# r8_1.net
KiCad netlist of a schematic drawn in EAGLE
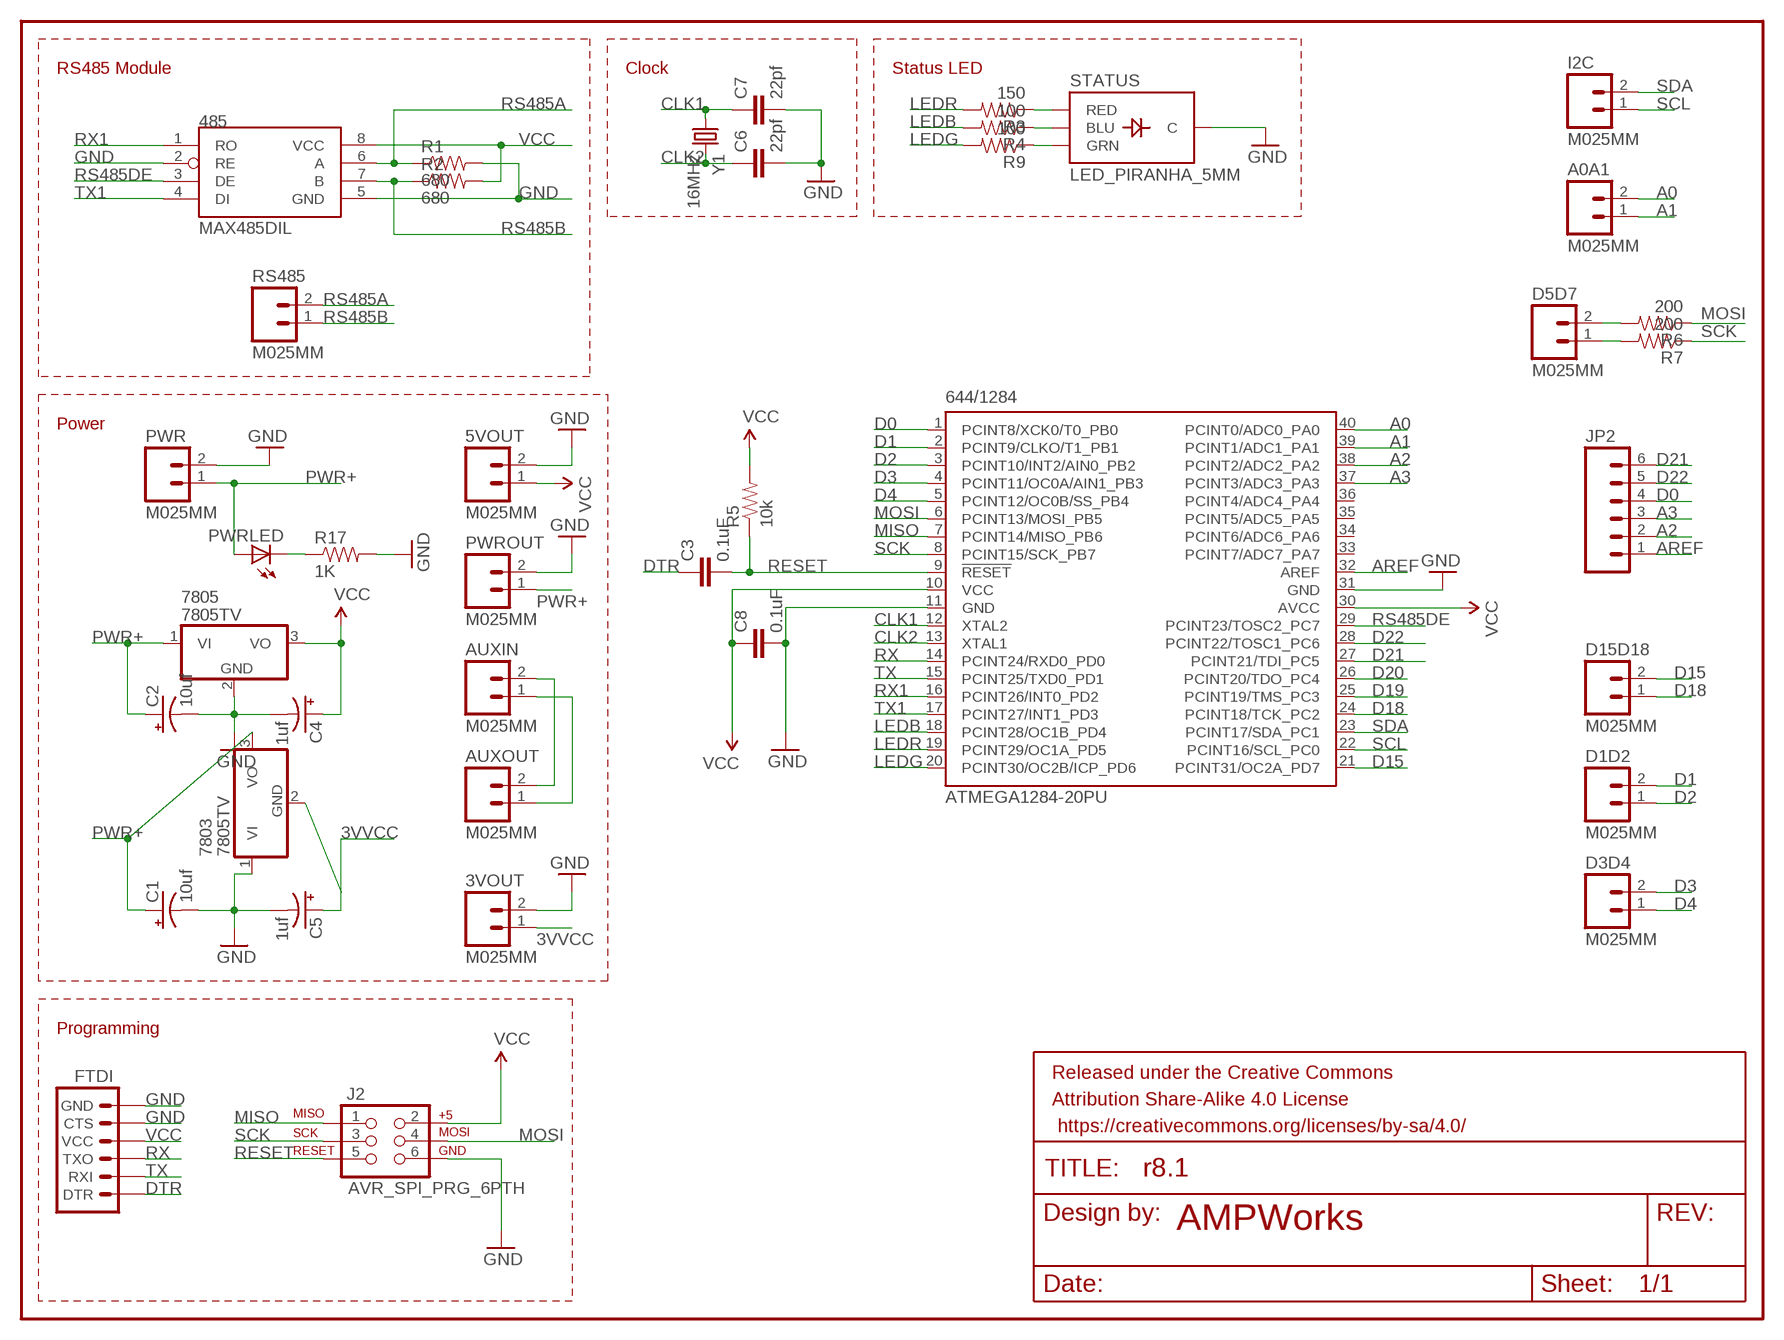
[diagram p0: schematic, sheet 1]

(export (version "E")
  (design (tool "Eeschema 10.0.6"))
  (components
    (comp (ref "3VOUT")
      (value "M025MM")
      (footprint "eagle-import:SCREWTERMINAL-5MM-2")
      (libsource (lib "eagle-import") (part "M025MM"))
    )
    (comp (ref "5VOUT")
      (value "M025MM")
      (footprint "eagle-import:SCREWTERMINAL-5MM-2")
      (libsource (lib "eagle-import") (part "M025MM"))
    )
    (comp (ref "485")
      (value "MAX485DIL")
      (footprint "eagle-import:DIL08")
      (libsource (lib "eagle-import") (part "MAX485DIL"))
    )
    (comp (ref "644/1284")
      (value "ATMEGA1284-20PU")
      (footprint "eagle-import:DIL40")
      (fields (field (name "MPN") "ATMEGA644-20PU"))
      (libsource (lib "eagle-import") (part "ATMEGA644-PU20"))
    )
    (comp (ref "7803")
      (value "7805TV")
      (footprint "eagle-import:TO220V")
      (libsource (lib "eagle-import") (part "78TV05"))
    )
    (comp (ref "7805")
      (value "7805TV")
      (footprint "eagle-import:TO220V")
      (libsource (lib "eagle-import") (part "78TV05"))
    )
    (comp (ref "A0A1")
      (value "M025MM")
      (footprint "eagle-import:SCREWTERMINAL-5MM-2")
      (libsource (lib "eagle-import") (part "M025MM"))
    )
    (comp (ref "AUXIN")
      (value "M025MM")
      (footprint "eagle-import:SCREWTERMINAL-5MM-2")
      (libsource (lib "eagle-import") (part "M025MM"))
    )
    (comp (ref "AUXOUT")
      (value "M025MM")
      (footprint "eagle-import:SCREWTERMINAL-5MM-2")
      (libsource (lib "eagle-import") (part "M025MM"))
    )
    (comp (ref "C1")
      (value "10uf")
      (footprint "eagle-import:CPOL-RADIAL-10UF-25V")
      (libsource (lib "eagle-import") (part "CAP_POLPTH2"))
    )
    (comp (ref "C2")
      (value "10uf")
      (footprint "eagle-import:CPOL-RADIAL-10UF-25V")
      (libsource (lib "eagle-import") (part "CAP_POLPTH2"))
    )
    (comp (ref "C3")
      (value "0.1uF")
      (footprint "eagle-import:CAP-PTH-SMALL")
      (libsource (lib "eagle-import") (part "CAPPTH"))
    )
    (comp (ref "C4")
      (value "1uf")
      (footprint "eagle-import:CPOL-RADIAL-10UF-25V")
      (libsource (lib "eagle-import") (part "CAP_POLPTH2"))
    )
    (comp (ref "C5")
      (value "1uf")
      (footprint "eagle-import:CPOL-RADIAL-10UF-25V")
      (libsource (lib "eagle-import") (part "CAP_POLPTH2"))
    )
    (comp (ref "C6")
      (value "22pf")
      (footprint "eagle-import:CAP-PTH-SMALL")
      (libsource (lib "eagle-import") (part "CAPPTH"))
    )
    (comp (ref "C7")
      (value "22pf")
      (footprint "eagle-import:CAP-PTH-SMALL")
      (libsource (lib "eagle-import") (part "CAPPTH"))
    )
    (comp (ref "C8")
      (value "0.1uF")
      (footprint "eagle-import:CAP-PTH-SMALL")
      (libsource (lib "eagle-import") (part "CAPPTH"))
    )
    (comp (ref "D1D2")
      (value "M025MM")
      (footprint "eagle-import:SCREWTERMINAL-5MM-2")
      (libsource (lib "eagle-import") (part "M025MM"))
    )
    (comp (ref "D3D4")
      (value "M025MM")
      (footprint "eagle-import:SCREWTERMINAL-5MM-2")
      (libsource (lib "eagle-import") (part "M025MM"))
    )
    (comp (ref "D5D7")
      (value "M025MM")
      (footprint "eagle-import:SCREWTERMINAL-5MM-2")
      (libsource (lib "eagle-import") (part "M025MM"))
    )
    (comp (ref "D15D18")
      (value "M025MM")
      (footprint "eagle-import:SCREWTERMINAL-5MM-2")
      (libsource (lib "eagle-import") (part "M025MM"))
    )
    (comp (ref "FRAME1")
      (value "FRAME-LETTER")
      (footprint "eagle-import:CREATIVE_COMMONS")
      (libsource (lib "eagle-import") (part "FRAME-LETTER"))
    )
    (comp (ref "FTDI")
      (value "ARDUINO_SERIAL_PROGRAMPTH")
      (footprint "eagle-import:1X06")
      (libsource (lib "eagle-import") (part "ARDUINO_SERIAL_PROGRAMPTH"))
    )
    (comp (ref "I2C")
      (value "M025MM")
      (footprint "eagle-import:SCREWTERMINAL-5MM-2")
      (libsource (lib "eagle-import") (part "M025MM"))
    )
    (comp (ref "J2")
      (value "AVR_SPI_PRG_6PTH")
      (footprint "eagle-import:2X3")
      (libsource (lib "eagle-import") (part "AVR_SPI_PRG_6PTH"))
    )
    (comp (ref "JP2")
      (value "M06NO_SILK")
      (footprint "eagle-import:1X06_NO_SILK")
      (libsource (lib "eagle-import") (part "M06NO_SILK"))
    )
    (comp (ref "PWR")
      (value "M025MM")
      (footprint "eagle-import:SCREWTERMINAL-5MM-2")
      (libsource (lib "eagle-import") (part "M025MM"))
    )
    (comp (ref "PWRLED")
      (value "LED5MM")
      (footprint "eagle-import:LED5MM")
      (libsource (lib "eagle-import") (part "LED5MM"))
    )
    (comp (ref "PWROUT")
      (value "M025MM")
      (footprint "eagle-import:SCREWTERMINAL-5MM-2")
      (libsource (lib "eagle-import") (part "M025MM"))
    )
    (comp (ref "R1")
      (value "680")
      (footprint "eagle-import:AXIAL-0.4")
      (libsource (lib "eagle-import") (part "SparkFun-Resistors_RESISTORPTH-1/4W"))
    )
    (comp (ref "R2")
      (value "680")
      (footprint "eagle-import:AXIAL-0.4")
      (libsource (lib "eagle-import") (part "SparkFun-Resistors_RESISTORPTH-1/4W"))
    )
    (comp (ref "R3")
      (value "150")
      (footprint "eagle-import:AXIAL-0.4")
      (libsource (lib "eagle-import") (part "RESISTORPTH-1/4W"))
    )
    (comp (ref "R4")
      (value "100")
      (footprint "eagle-import:AXIAL-0.4")
      (libsource (lib "eagle-import") (part "RESISTORPTH-1/4W"))
    )
    (comp (ref "R5")
      (value "10k")
      (footprint "eagle-import:AXIAL-0.4")
      (libsource (lib "eagle-import") (part "RESISTORPTH-1/4W"))
    )
    (comp (ref "R6")
      (value "200")
      (footprint "eagle-import:AXIAL-0.4")
      (libsource (lib "eagle-import") (part "RESISTORPTH-1/4W"))
    )
    (comp (ref "R7")
      (value "200")
      (footprint "eagle-import:AXIAL-0.4")
      (libsource (lib "eagle-import") (part "RESISTORPTH-1/4W"))
    )
    (comp (ref "R9")
      (value "100")
      (footprint "eagle-import:AXIAL-0.4")
      (libsource (lib "eagle-import") (part "RESISTORPTH-1/4W"))
    )
    (comp (ref "R17")
      (value "1K")
      (footprint "eagle-import:AXIAL-0.4")
      (libsource (lib "eagle-import") (part "SparkFun-Resistors_RESISTORPTH-1/4W"))
    )
    (comp (ref "RS485")
      (value "M025MM")
      (footprint "eagle-import:SCREWTERMINAL-5MM-2")
      (libsource (lib "eagle-import") (part "M025MM"))
    )
    (comp (ref "STATUS")
      (value "LED_PIRANHA_5MM")
      (footprint "eagle-import:LED_PIRANHA_5MM")
      (libsource (lib "eagle-import") (part "LED_PIRANHA_5MM"))
    )
    (comp (ref "Y1")
      (value "16MHz")
      (footprint "eagle-import:HC49US")
      (libsource (lib "eagle-import") (part "CRYSTALHC49US"))
    )
  )
  (nets
    (net (code "1") (name "/3VVCC") (class "Default")
      (node (ref "3VOUT") (pin "1") (pinfunction "1_1") (pintype "passive"))
      (node (ref "7803") (pin "2") (pinfunction "GND_2") (pintype "passive"))
      (node (ref "C5") (pin "1") (pinfunction "+_1") (pintype "passive"))
    )
    (net (code "2") (name "/A0") (class "Default")
      (node (ref "644/1284") (pin "40") (pinfunction "PCINT0/ADC0_PA0_40") (pintype "bidirectional"))
      (node (ref "A0A1") (pin "2") (pinfunction "2_2") (pintype "passive"))
    )
    (net (code "3") (name "/A1") (class "Default")
      (node (ref "644/1284") (pin "39") (pinfunction "PCINT1/ADC1_PA1_39") (pintype "bidirectional"))
      (node (ref "A0A1") (pin "1") (pinfunction "1_1") (pintype "passive"))
    )
    (net (code "4") (name "/A2") (class "Default")
      (node (ref "644/1284") (pin "38") (pinfunction "PCINT2/ADC2_PA2_38") (pintype "bidirectional"))
      (node (ref "JP2") (pin "2") (pinfunction "2_2") (pintype "passive"))
    )
    (net (code "5") (name "/A3") (class "Default")
      (node (ref "644/1284") (pin "37") (pinfunction "PCINT3/ADC3_PA3_37") (pintype "bidirectional"))
      (node (ref "JP2") (pin "3") (pinfunction "3_3") (pintype "passive"))
    )
    (net (code "6") (name "/AREF") (class "Default")
      (node (ref "644/1284") (pin "32") (pinfunction "AREF_32") (pintype "passive"))
      (node (ref "JP2") (pin "1") (pinfunction "1_1") (pintype "passive"))
    )
    (net (code "7") (name "/CLK1") (class "Default")
      (node (ref "644/1284") (pin "12") (pinfunction "XTAL2_12") (pintype "output"))
      (node (ref "C7") (pin "1") (pinfunction "1_1") (pintype "passive"))
      (node (ref "Y1") (pin "1") (pinfunction "1_1") (pintype "passive"))
    )
    (net (code "8") (name "/CLK2") (class "Default")
      (node (ref "644/1284") (pin "13") (pinfunction "XTAL1_13") (pintype "input"))
      (node (ref "C6") (pin "1") (pinfunction "1_1") (pintype "passive"))
      (node (ref "Y1") (pin "2") (pinfunction "2_2") (pintype "passive"))
    )
    (net (code "9") (name "/D0") (class "Default")
      (node (ref "644/1284") (pin "1") (pinfunction "PCINT8/XCK0/T0_PB0_1") (pintype "bidirectional"))
      (node (ref "JP2") (pin "4") (pinfunction "4_4") (pintype "passive"))
    )
    (net (code "10") (name "/D1") (class "Default")
      (node (ref "644/1284") (pin "2") (pinfunction "PCINT9/CLKO/T1_PB1_2") (pintype "bidirectional"))
      (node (ref "D1D2") (pin "2") (pinfunction "2_2") (pintype "passive"))
    )
    (net (code "11") (name "/D2") (class "Default")
      (node (ref "644/1284") (pin "3") (pinfunction "PCINT10/INT2/AIN0_PB2_3") (pintype "bidirectional"))
      (node (ref "D1D2") (pin "1") (pinfunction "1_1") (pintype "passive"))
    )
    (net (code "12") (name "/D3") (class "Default")
      (node (ref "644/1284") (pin "4") (pinfunction "PCINT11/OC0A/AIN1_PB3_4") (pintype "bidirectional"))
      (node (ref "D3D4") (pin "2") (pinfunction "2_2") (pintype "passive"))
    )
    (net (code "13") (name "/D4") (class "Default")
      (node (ref "644/1284") (pin "5") (pinfunction "PCINT12/OC0B/SS_PB4_5") (pintype "bidirectional"))
      (node (ref "D3D4") (pin "1") (pinfunction "1_1") (pintype "passive"))
    )
    (net (code "14") (name "/D15") (class "Default")
      (node (ref "644/1284") (pin "21") (pinfunction "PCINT31/OC2A_PD7_21") (pintype "bidirectional"))
      (node (ref "D15D18") (pin "2") (pinfunction "2_2") (pintype "passive"))
    )
    (net (code "15") (name "/D18") (class "Default")
      (node (ref "644/1284") (pin "24") (pinfunction "PCINT18/TCK_PC2_24") (pintype "bidirectional"))
      (node (ref "D15D18") (pin "1") (pinfunction "1_1") (pintype "passive"))
    )
    (net (code "16") (name "/D19") (class "Default")
      (node (ref "644/1284") (pin "25") (pinfunction "PCINT19/TMS_PC3_25") (pintype "bidirectional"))
    )
    (net (code "17") (name "/D20") (class "Default")
      (node (ref "644/1284") (pin "26") (pinfunction "PCINT20/TDO_PC4_26") (pintype "bidirectional"))
    )
    (net (code "18") (name "/D21") (class "Default")
      (node (ref "644/1284") (pin "27") (pinfunction "PCINT21/TDI_PC5_27") (pintype "bidirectional"))
      (node (ref "JP2") (pin "6") (pinfunction "6_6") (pintype "passive"))
    )
    (net (code "19") (name "/D22") (class "Default")
      (node (ref "644/1284") (pin "28") (pinfunction "PCINT22/TOSC1_PC6_28") (pintype "bidirectional"))
      (node (ref "JP2") (pin "5") (pinfunction "5_5") (pintype "passive"))
    )
    (net (code "20") (name "/DTR") (class "Default")
      (node (ref "C3") (pin "1") (pinfunction "1_1") (pintype "passive"))
      (node (ref "FTDI") (pin "DTR") (pinfunction "DTR_DTR") (pintype "passive"))
    )
    (net (code "21") (name "/LEDB") (class "Default")
      (node (ref "644/1284") (pin "18") (pinfunction "PCINT28/OC1B_PD4_18") (pintype "bidirectional"))
      (node (ref "R4") (pin "P$2") (pinfunction "2_P$2") (pintype "passive"))
    )
    (net (code "22") (name "/LEDG") (class "Default")
      (node (ref "644/1284") (pin "20") (pinfunction "PCINT30/OC2B/ICP_PD6_20") (pintype "bidirectional"))
      (node (ref "R9") (pin "P$2") (pinfunction "2_P$2") (pintype "passive"))
    )
    (net (code "23") (name "/LEDR") (class "Default")
      (node (ref "644/1284") (pin "19") (pinfunction "PCINT29/OC1A_PD5_19") (pintype "bidirectional"))
      (node (ref "R3") (pin "P$2") (pinfunction "2_P$2") (pintype "passive"))
    )
    (net (code "24") (name "/MISO") (class "Default")
      (node (ref "644/1284") (pin "7") (pinfunction "PCINT14/MISO_PB6_7") (pintype "bidirectional"))
      (node (ref "J2") (pin "1") (pinfunction "1_1") (pintype "passive"))
    )
    (net (code "25") (name "/MOSI") (class "Default")
      (node (ref "644/1284") (pin "6") (pinfunction "PCINT13/MOSI_PB5_6") (pintype "bidirectional"))
      (node (ref "J2") (pin "4") (pinfunction "4_4") (pintype "passive"))
      (node (ref "R6") (pin "P$1") (pinfunction "1_P$1") (pintype "passive"))
    )
    (net (code "26") (name "/PWR+") (class "Default")
      (node (ref "7803") (pin "3") (pinfunction "VO_3") (pintype "passive"))
      (node (ref "7805") (pin "1") (pinfunction "VI_1") (pintype "input"))
      (node (ref "C1") (pin "1") (pinfunction "+_1") (pintype "passive"))
      (node (ref "C2") (pin "1") (pinfunction "+_1") (pintype "passive"))
      (node (ref "PWR") (pin "1") (pinfunction "1_1") (pintype "passive"))
      (node (ref "PWRLED") (pin "A") (pinfunction "A_A") (pintype "passive"))
      (node (ref "PWROUT") (pin "1") (pinfunction "1_1") (pintype "passive"))
    )
    (net (code "27") (name "/RESET") (class "Default")
      (node (ref "644/1284") (pin "9") (pinfunction "~{RESET}_9") (pintype "input"))
      (node (ref "C3") (pin "2") (pinfunction "2_2") (pintype "passive"))
      (node (ref "J2") (pin "5") (pinfunction "5_5") (pintype "passive"))
      (node (ref "R5") (pin "P$1") (pinfunction "1_P$1") (pintype "passive"))
    )
    (net (code "28") (name "/RS485A") (class "Default")
      (node (ref "485") (pin "6") (pinfunction "A_6") (pintype "bidirectional"))
      (node (ref "R1") (pin "P$1") (pinfunction "1_P$1") (pintype "passive"))
      (node (ref "RS485") (pin "2") (pinfunction "2_2") (pintype "passive"))
    )
    (net (code "29") (name "/RS485B") (class "Default")
      (node (ref "485") (pin "7") (pinfunction "B_7") (pintype "bidirectional"))
      (node (ref "R2") (pin "P$1") (pinfunction "1_P$1") (pintype "passive"))
      (node (ref "RS485") (pin "1") (pinfunction "1_1") (pintype "passive"))
    )
    (net (code "30") (name "/RS485DE") (class "Default")
      (node (ref "485") (pin "3") (pinfunction "DE_3") (pintype "bidirectional"))
      (node (ref "644/1284") (pin "29") (pinfunction "PCINT23/TOSC2_PC7_29") (pintype "bidirectional"))
    )
    (net (code "31") (name "/RX") (class "Default")
      (node (ref "644/1284") (pin "14") (pinfunction "PCINT24/RXD0_PD0_14") (pintype "bidirectional"))
      (node (ref "FTDI") (pin "TXO") (pinfunction "TXO_TXO") (pintype "passive"))
    )
    (net (code "32") (name "/RX1") (class "Default")
      (node (ref "485") (pin "1") (pinfunction "RO_1") (pintype "bidirectional"))
      (node (ref "644/1284") (pin "16") (pinfunction "PCINT26/INT0_PD2_16") (pintype "bidirectional"))
    )
    (net (code "33") (name "/SCK") (class "Default")
      (node (ref "644/1284") (pin "8") (pinfunction "PCINT15/SCK_PB7_8") (pintype "bidirectional"))
      (node (ref "J2") (pin "3") (pinfunction "3_3") (pintype "passive"))
      (node (ref "R7") (pin "P$1") (pinfunction "1_P$1") (pintype "passive"))
    )
    (net (code "34") (name "/SCL") (class "Default")
      (node (ref "644/1284") (pin "22") (pinfunction "PCINT16/SCL_PC0_22") (pintype "bidirectional"))
      (node (ref "I2C") (pin "1") (pinfunction "1_1") (pintype "passive"))
    )
    (net (code "35") (name "/SDA") (class "Default")
      (node (ref "644/1284") (pin "23") (pinfunction "PCINT17/SDA_PC1_23") (pintype "bidirectional"))
      (node (ref "I2C") (pin "2") (pinfunction "2_2") (pintype "passive"))
    )
    (net (code "36") (name "/TX") (class "Default")
      (node (ref "644/1284") (pin "15") (pinfunction "PCINT25/TXD0_PD1_15") (pintype "bidirectional"))
      (node (ref "FTDI") (pin "RXI") (pinfunction "RXI_RXI") (pintype "passive"))
    )
    (net (code "37") (name "/TX1") (class "Default")
      (node (ref "485") (pin "4") (pinfunction "DI_4") (pintype "bidirectional"))
      (node (ref "644/1284") (pin "17") (pinfunction "PCINT27/INT1_PD3_17") (pintype "bidirectional"))
    )
    (net (code "38") (name "GND") (class "Default")
      (node (ref "3VOUT") (pin "2") (pinfunction "2_2") (pintype "passive"))
      (node (ref "485") (pin "2") (pinfunction "RE_2") (pintype "bidirectional"))
      (node (ref "485") (pin "5") (pinfunction "GND_5") (pintype "bidirectional"))
      (node (ref "5VOUT") (pin "2") (pinfunction "2_2") (pintype "passive"))
      (node (ref "644/1284") (pin "11") (pinfunction "GND_11") (pintype "power_in"))
      (node (ref "644/1284") (pin "31") (pinfunction "GND_31") (pintype "power_in"))
      (node (ref "7803") (pin "1") (pinfunction "VI_1") (pintype "input"))
      (node (ref "7805") (pin "2") (pinfunction "GND_2") (pintype "passive"))
      (node (ref "C1") (pin "2") (pinfunction "-_2") (pintype "passive"))
      (node (ref "C2") (pin "2") (pinfunction "-_2") (pintype "passive"))
      (node (ref "C4") (pin "2") (pinfunction "-_2") (pintype "passive"))
      (node (ref "C5") (pin "2") (pinfunction "-_2") (pintype "passive"))
      (node (ref "C6") (pin "2") (pinfunction "2_2") (pintype "passive"))
      (node (ref "C7") (pin "2") (pinfunction "2_2") (pintype "passive"))
      (node (ref "C8") (pin "2") (pinfunction "2_2") (pintype "passive"))
      (node (ref "FTDI") (pin "CTS") (pinfunction "CTS_CTS") (pintype "passive"))
      (node (ref "FTDI") (pin "GND") (pinfunction "GND_GND") (pintype "passive"))
      (node (ref "J2") (pin "6") (pinfunction "6_6") (pintype "passive"))
      (node (ref "PWR") (pin "2") (pinfunction "2_2") (pintype "passive"))
      (node (ref "PWROUT") (pin "2") (pinfunction "2_2") (pintype "passive"))
      (node (ref "R1") (pin "P$2") (pinfunction "2_P$2") (pintype "passive"))
      (node (ref "R17") (pin "P$2") (pinfunction "2_P$2") (pintype "passive"))
      (node (ref "STATUS") (pin "-") (pinfunction "C_-") (pintype "bidirectional"))
    )
    (net (code "39") (name "Net-(AUXIN-Pad1)") (class "Default")
      (node (ref "AUXIN") (pin "1") (pinfunction "1_1") (pintype "passive"))
      (node (ref "AUXOUT") (pin "1") (pinfunction "1_1") (pintype "passive"))
    )
    (net (code "40") (name "Net-(AUXIN-Pad2)") (class "Default")
      (node (ref "AUXIN") (pin "2") (pinfunction "2_2") (pintype "passive"))
      (node (ref "AUXOUT") (pin "2") (pinfunction "2_2") (pintype "passive"))
    )
    (net (code "41") (name "Net-(PWRLED-C)") (class "Default")
      (node (ref "PWRLED") (pin "K") (pinfunction "C_K") (pintype "passive"))
      (node (ref "R17") (pin "P$1") (pinfunction "1_P$1") (pintype "passive"))
    )
    (net (code "42") (name "Net-(R3-1)") (class "Default")
      (node (ref "R3") (pin "P$1") (pinfunction "1_P$1") (pintype "passive"))
      (node (ref "STATUS") (pin "R") (pinfunction "RED_R") (pintype "bidirectional"))
    )
    (net (code "43") (name "Net-(R4-1)") (class "Default")
      (node (ref "R4") (pin "P$1") (pinfunction "1_P$1") (pintype "passive"))
      (node (ref "STATUS") (pin "B") (pinfunction "BLU_B") (pintype "bidirectional"))
    )
    (net (code "44") (name "Net-(R6-2)") (class "Default")
      (node (ref "D5D7") (pin "2") (pinfunction "2_2") (pintype "passive"))
      (node (ref "R6") (pin "P$2") (pinfunction "2_P$2") (pintype "passive"))
    )
    (net (code "45") (name "Net-(R7-2)") (class "Default")
      (node (ref "D5D7") (pin "1") (pinfunction "1_1") (pintype "passive"))
      (node (ref "R7") (pin "P$2") (pinfunction "2_P$2") (pintype "passive"))
    )
    (net (code "46") (name "Net-(R9-1)") (class "Default")
      (node (ref "R9") (pin "P$1") (pinfunction "1_P$1") (pintype "passive"))
      (node (ref "STATUS") (pin "G") (pinfunction "GRN_G") (pintype "bidirectional"))
    )
    (net (code "47") (name "VCC") (class "Default")
      (node (ref "485") (pin "8") (pinfunction "VCC_8") (pintype "bidirectional"))
      (node (ref "5VOUT") (pin "1") (pinfunction "1_1") (pintype "passive"))
      (node (ref "644/1284") (pin "10") (pinfunction "VCC_10") (pintype "power_in"))
      (node (ref "644/1284") (pin "30") (pinfunction "AVCC_30") (pintype "power_in"))
      (node (ref "7805") (pin "3") (pinfunction "VO_3") (pintype "passive"))
      (node (ref "C4") (pin "1") (pinfunction "+_1") (pintype "passive"))
      (node (ref "C8") (pin "1") (pinfunction "1_1") (pintype "passive"))
      (node (ref "FTDI") (pin "VCC") (pinfunction "VCC_VCC") (pintype "passive"))
      (node (ref "J2") (pin "2") (pinfunction "2_2") (pintype "passive"))
      (node (ref "R2") (pin "P$2") (pinfunction "2_P$2") (pintype "passive"))
      (node (ref "R5") (pin "P$2") (pinfunction "2_P$2") (pintype "passive"))
    )
    (net (code "48") (name "unconnected-(644/1284-PCINT4{slash}ADC4_PA4-Pad36)") (class "Default")
      (node (ref "644/1284") (pin "36") (pinfunction "PCINT4/ADC4_PA4_36") (pintype "bidirectional"))
    )
    (net (code "49") (name "unconnected-(644/1284-PCINT5{slash}ADC5_PA5-Pad35)") (class "Default")
      (node (ref "644/1284") (pin "35") (pinfunction "PCINT5/ADC5_PA5_35") (pintype "bidirectional"))
    )
    (net (code "50") (name "unconnected-(644/1284-PCINT6{slash}ADC6_PA6-Pad34)") (class "Default")
      (node (ref "644/1284") (pin "34") (pinfunction "PCINT6/ADC6_PA6_34") (pintype "bidirectional"))
    )
    (net (code "51") (name "unconnected-(644/1284-PCINT7{slash}ADC7_PA7-Pad33)") (class "Default")
      (node (ref "644/1284") (pin "33") (pinfunction "PCINT7/ADC7_PA7_33") (pintype "bidirectional"))
    )
  )
)
